# Alimentaci_n.net
KiCad netlist of a schematic drawn in Altium Designer
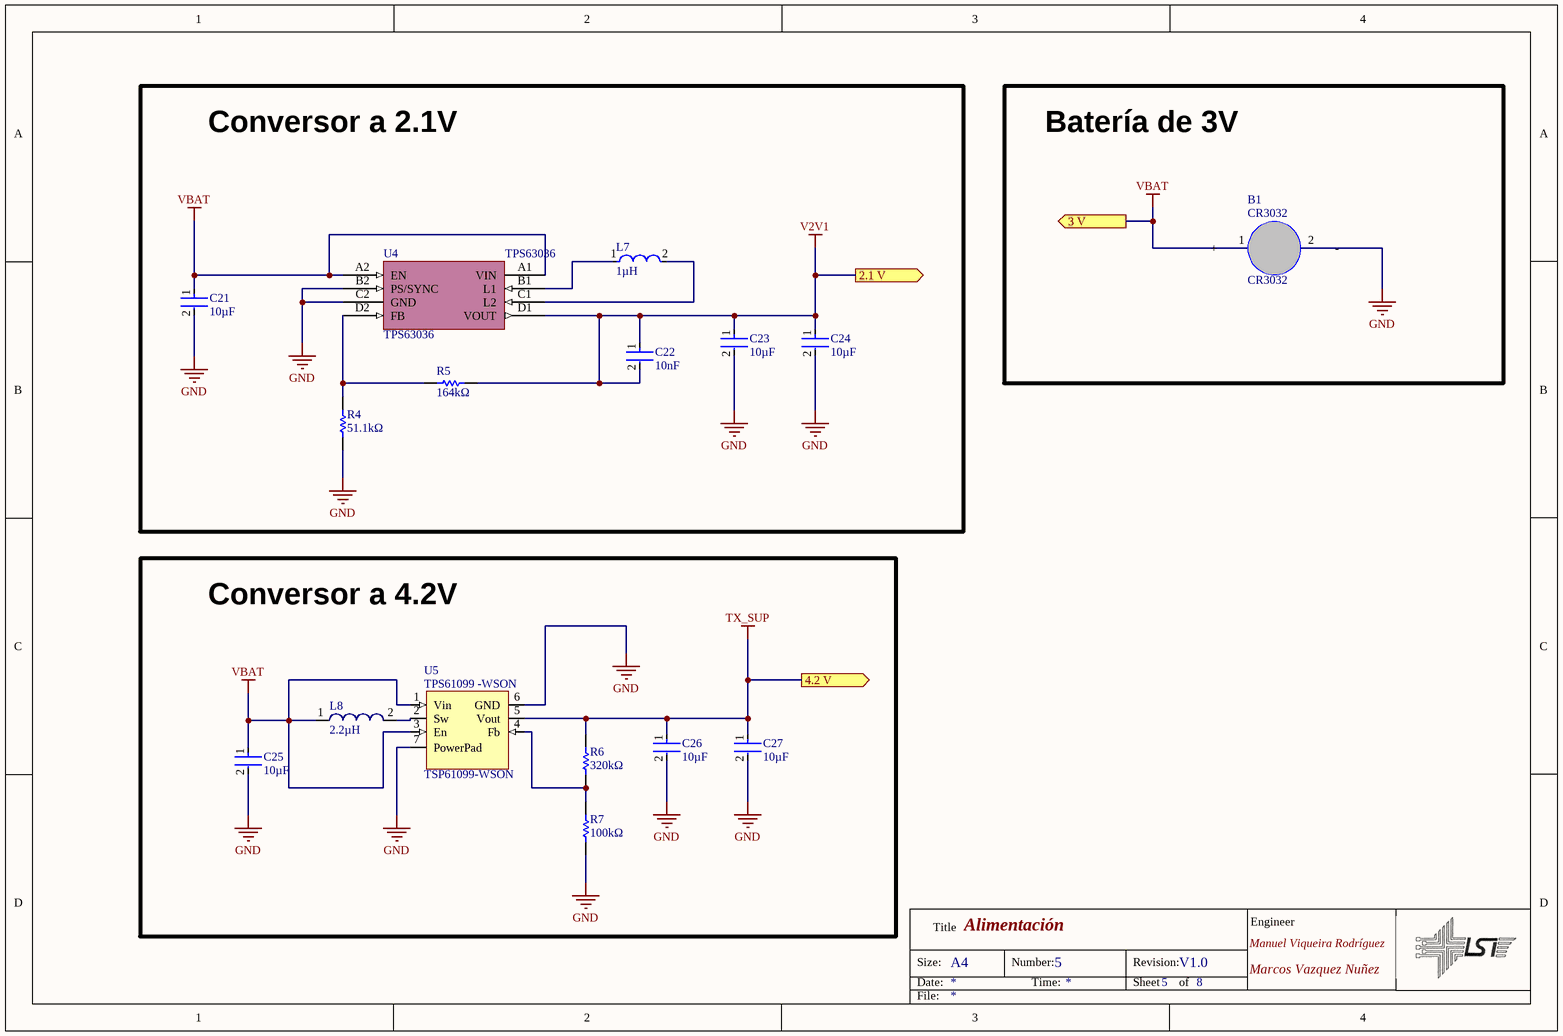
[diagram p0: Alimentación.SchDoc]

(export (version "E")
  (design (tool "Eeschema 10.0.6"))
  (components
    (comp (ref "B1") (value "CR3032") (footprint "CR3032") (libsource (lib "DEOP2021") (part "CR3032")))
    (comp (ref "C21")
      (value "10µF")
      (footprint "FP-CL10-IPC_B")
      (description "Cap Ceramic 10uF 10V X5R ±10% Pad SMD 0603 +85°C T/R")
      (fields (field (name "TOLERANCE") "10%"))
      (libsource (lib "Altium Content Vault") (part "b4654b650e69147ec39a6b967a45e02"))
    )
    (comp (ref "C22")
      (value "10nF")
      (footprint "FP-CL10-IPC_C")
      (description "Cap Ceramic 10nF 50V X7R ±20% Pad SMD 0603 +125°C T/R")
      (fields (field (name "TOLERANCE") "20%"))
      (libsource (lib "Altium Content Vault") (part "b4654b650e69147ec39a6b967a45e02"))
    )
    (comp (ref "C23")
      (value "10µF")
      (footprint "FP-CL10-IPC_B")
      (description "Cap Ceramic 10uF 10V X5R ±10% Pad SMD 0603 +85°C T/R")
      (fields (field (name "TOLERANCE") "10%"))
      (libsource (lib "Altium Content Vault") (part "b4654b650e69147ec39a6b967a45e02"))
    )
    (comp (ref "C24")
      (value "10µF")
      (footprint "FP-CL10-IPC_B")
      (description "Cap Ceramic 10uF 10V X5R ±10% Pad SMD 0603 +85°C T/R")
      (fields (field (name "TOLERANCE") "10%"))
      (libsource (lib "Altium Content Vault") (part "b4654b650e69147ec39a6b967a45e02"))
    )
    (comp (ref "C25")
      (value "10µF")
      (footprint "FP-CL10-IPC_B")
      (description "Cap Ceramic 10uF 10V X5R ±10% Pad SMD 0603 +85°C T/R")
      (fields (field (name "TOLERANCE") "10%"))
      (libsource (lib "Altium Content Vault") (part "b4654b650e69147ec39a6b967a45e02"))
    )
    (comp (ref "C26")
      (value "10µF")
      (footprint "FP-CL10-IPC_B")
      (description "Cap Ceramic 10uF 10V X5R ±10% Pad SMD 0603 +85°C T/R")
      (fields (field (name "TOLERANCE") "10%"))
      (libsource (lib "Altium Content Vault") (part "b4654b650e69147ec39a6b967a45e02"))
    )
    (comp (ref "C27")
      (value "10µF")
      (footprint "FP-CL10-IPC_B")
      (description "Cap Ceramic 10uF 10V X5R ±10% Pad SMD 0603 +85°C T/R")
      (fields (field (name "TOLERANCE") "10%"))
      (libsource (lib "Altium Content Vault") (part "b4654b650e69147ec39a6b967a45e02"))
    )
    (comp (ref "L7")
      (value "1µH")
      (footprint "FP-MLZ1608-MFG")
      (description "FIXED IND 1UH 600MA 150 MOHM SMD")
      (fields (field (name "MANUFACTURER PART NUMBER") "MLZ1608A1R0WT000") (field (name "TOLERANCE") "20%"))
      (libsource (lib "Altium Content Vault") (part "725321dda6339637d4d059423bc1c3c"))
    )
    (comp (ref "L8")
      (value "2.2µH")
      (footprint "SMD 2508")
      (description "Power Multilayer Inductor WE-MAPI, L=2.2µH")
      (fields (field (name "PARTNUMBER") "74438322022") (field (name "MANUFACTURER") "Wuerth Elektronik"))
      (libsource (lib "Altium Content Vault") (part "WE-IND-INDUCTOR-2"))
    )
    (comp (ref "R4")
      (value "51.1kΩ")
      (footprint "RESC0603X28X15ML05T05")
      (fields (field (name "MANUFACTURER") "Vishay Dale") (field (name "PART NUMBER") "CRCW020120K0JNED"))
      (libsource (lib "Altium Content Vault") (part "RES"))
    )
    (comp (ref "R5")
      (value "164kΩ")
      (footprint "RESC0603X28X15ML05T05")
      (fields (field (name "MANUFACTURER") "Vishay Dale") (field (name "PART NUMBER") "CRCW020120K0JNED"))
      (libsource (lib "Altium Content Vault") (part "RES"))
    )
    (comp (ref "R6")
      (value "320kΩ")
      (footprint "RESC0603X28X15ML05T05")
      (fields (field (name "MANUFACTURER") "Vishay Dale") (field (name "PART NUMBER") "CRCW020120K0JNED"))
      (libsource (lib "Altium Content Vault") (part "RES"))
    )
    (comp (ref "R7")
      (value "100kΩ")
      (footprint "RESC0603X28X15ML05T05")
      (fields (field (name "MANUFACTURER") "Vishay Dale") (field (name "PART NUMBER") "CRCW020120K0JNED"))
      (libsource (lib "Altium Content Vault") (part "RES"))
    )
    (comp (ref "U4") (value "TPS63036") (footprint "tps63036") (libsource (lib "DEOP2021") (part "TPS63036")))
    (comp (ref "U5")
      (value "TSP61099-WSON")
      (footprint "SOP6")
      (libsource (lib "DEOP2021") (part "TSP61099-WSON"))
    )
  )
  (nets
    (net (code "1") (name "GND") (class "Default")
      (node (ref "B1") (pin "2") (pinfunction "-_2") (pintype "passive"))
      (node (ref "C21") (pin "2") (pinfunction "2_2") (pintype "passive"))
      (node (ref "C23") (pin "2") (pinfunction "2_2") (pintype "passive"))
      (node (ref "C24") (pin "2") (pinfunction "2_2") (pintype "passive"))
      (node (ref "C25") (pin "2") (pinfunction "2_2") (pintype "passive"))
      (node (ref "C26") (pin "2") (pinfunction "2_2") (pintype "passive"))
      (node (ref "C27") (pin "2") (pinfunction "2_2") (pintype "passive"))
      (node (ref "R4") (pin "1") (pinfunction "1_1") (pintype "passive"))
      (node (ref "R7") (pin "1") (pinfunction "1_1") (pintype "passive"))
      (node (ref "U4") (pin "B2") (pinfunction "PS/SYNC_B2") (pintype "input"))
      (node (ref "U4") (pin "C2") (pinfunction "GND_C2") (pintype "power_in"))
      (node (ref "U5") (pin "6") (pinfunction "GND_6") (pintype "power_in"))
      (node (ref "U5") (pin "7") (pinfunction "PowerPad_7") (pintype "power_in"))
    )
    (net (code "2") (name "Net-(U4-FB)") (class "Default")
      (node (ref "R4") (pin "2") (pinfunction "2_2") (pintype "passive"))
      (node (ref "R5") (pin "1") (pinfunction "1_1") (pintype "passive"))
      (node (ref "U4") (pin "D2") (pinfunction "FB_D2") (pintype "input"))
    )
    (net (code "3") (name "Net-(U4-L1)") (class "Default")
      (node (ref "L7") (pin "1") (pinfunction "1_1") (pintype "passive"))
      (node (ref "U4") (pin "B1") (pinfunction "L1_B1") (pintype "input"))
    )
    (net (code "4") (name "Net-(U4-L2)") (class "Default")
      (node (ref "L7") (pin "2") (pinfunction "2_2") (pintype "passive"))
      (node (ref "U4") (pin "C1") (pinfunction "L2_C1") (pintype "input"))
    )
    (net (code "5") (name "Net-(U5-Fb)") (class "Default")
      (node (ref "R6") (pin "1") (pinfunction "1_1") (pintype "passive"))
      (node (ref "R7") (pin "2") (pinfunction "2_2") (pintype "passive"))
      (node (ref "U5") (pin "4") (pinfunction "Fb_4") (pintype "input"))
    )
    (net (code "6") (name "Net-(U5-Sw)") (class "Default")
      (node (ref "L8") (pin "2") (pinfunction "2_2") (pintype "passive"))
      (node (ref "U5") (pin "2") (pinfunction "Sw_2") (pintype "power_in"))
    )
    (net (code "7") (name "TX_SUP") (class "Default")
      (node (ref "C26") (pin "1") (pinfunction "1_1") (pintype "passive"))
      (node (ref "C27") (pin "1") (pinfunction "1_1") (pintype "passive"))
      (node (ref "R6") (pin "2") (pinfunction "2_2") (pintype "passive"))
      (node (ref "U5") (pin "5") (pinfunction "Vout_5") (pintype "power_in"))
    )
    (net (code "8") (name "V2V1") (class "Default")
      (node (ref "C22") (pin "1") (pinfunction "1_1") (pintype "passive"))
      (node (ref "C22") (pin "2") (pinfunction "2_2") (pintype "passive"))
      (node (ref "C23") (pin "1") (pinfunction "1_1") (pintype "passive"))
      (node (ref "C24") (pin "1") (pinfunction "1_1") (pintype "passive"))
      (node (ref "R5") (pin "2") (pinfunction "2_2") (pintype "passive"))
      (node (ref "U4") (pin "D1") (pinfunction "VOUT_D1") (pintype "output"))
    )
    (net (code "9") (name "VBAT") (class "Default")
      (node (ref "B1") (pin "1") (pinfunction "+_1") (pintype "passive"))
      (node (ref "C21") (pin "1") (pinfunction "1_1") (pintype "passive"))
      (node (ref "C25") (pin "1") (pinfunction "1_1") (pintype "passive"))
      (node (ref "L8") (pin "1") (pinfunction "1_1") (pintype "passive"))
      (node (ref "U4") (pin "A1") (pinfunction "VIN_A1") (pintype "power_in"))
      (node (ref "U4") (pin "A2") (pinfunction "EN_A2") (pintype "input"))
      (node (ref "U5") (pin "1") (pinfunction "Vin_1") (pintype "input"))
      (node (ref "U5") (pin "3") (pinfunction "En_3") (pintype "input"))
    )
  )
)
